# SCH_shield_test_2024-01-20.net
KiCad netlist of a schematic drawn in EasyEDA
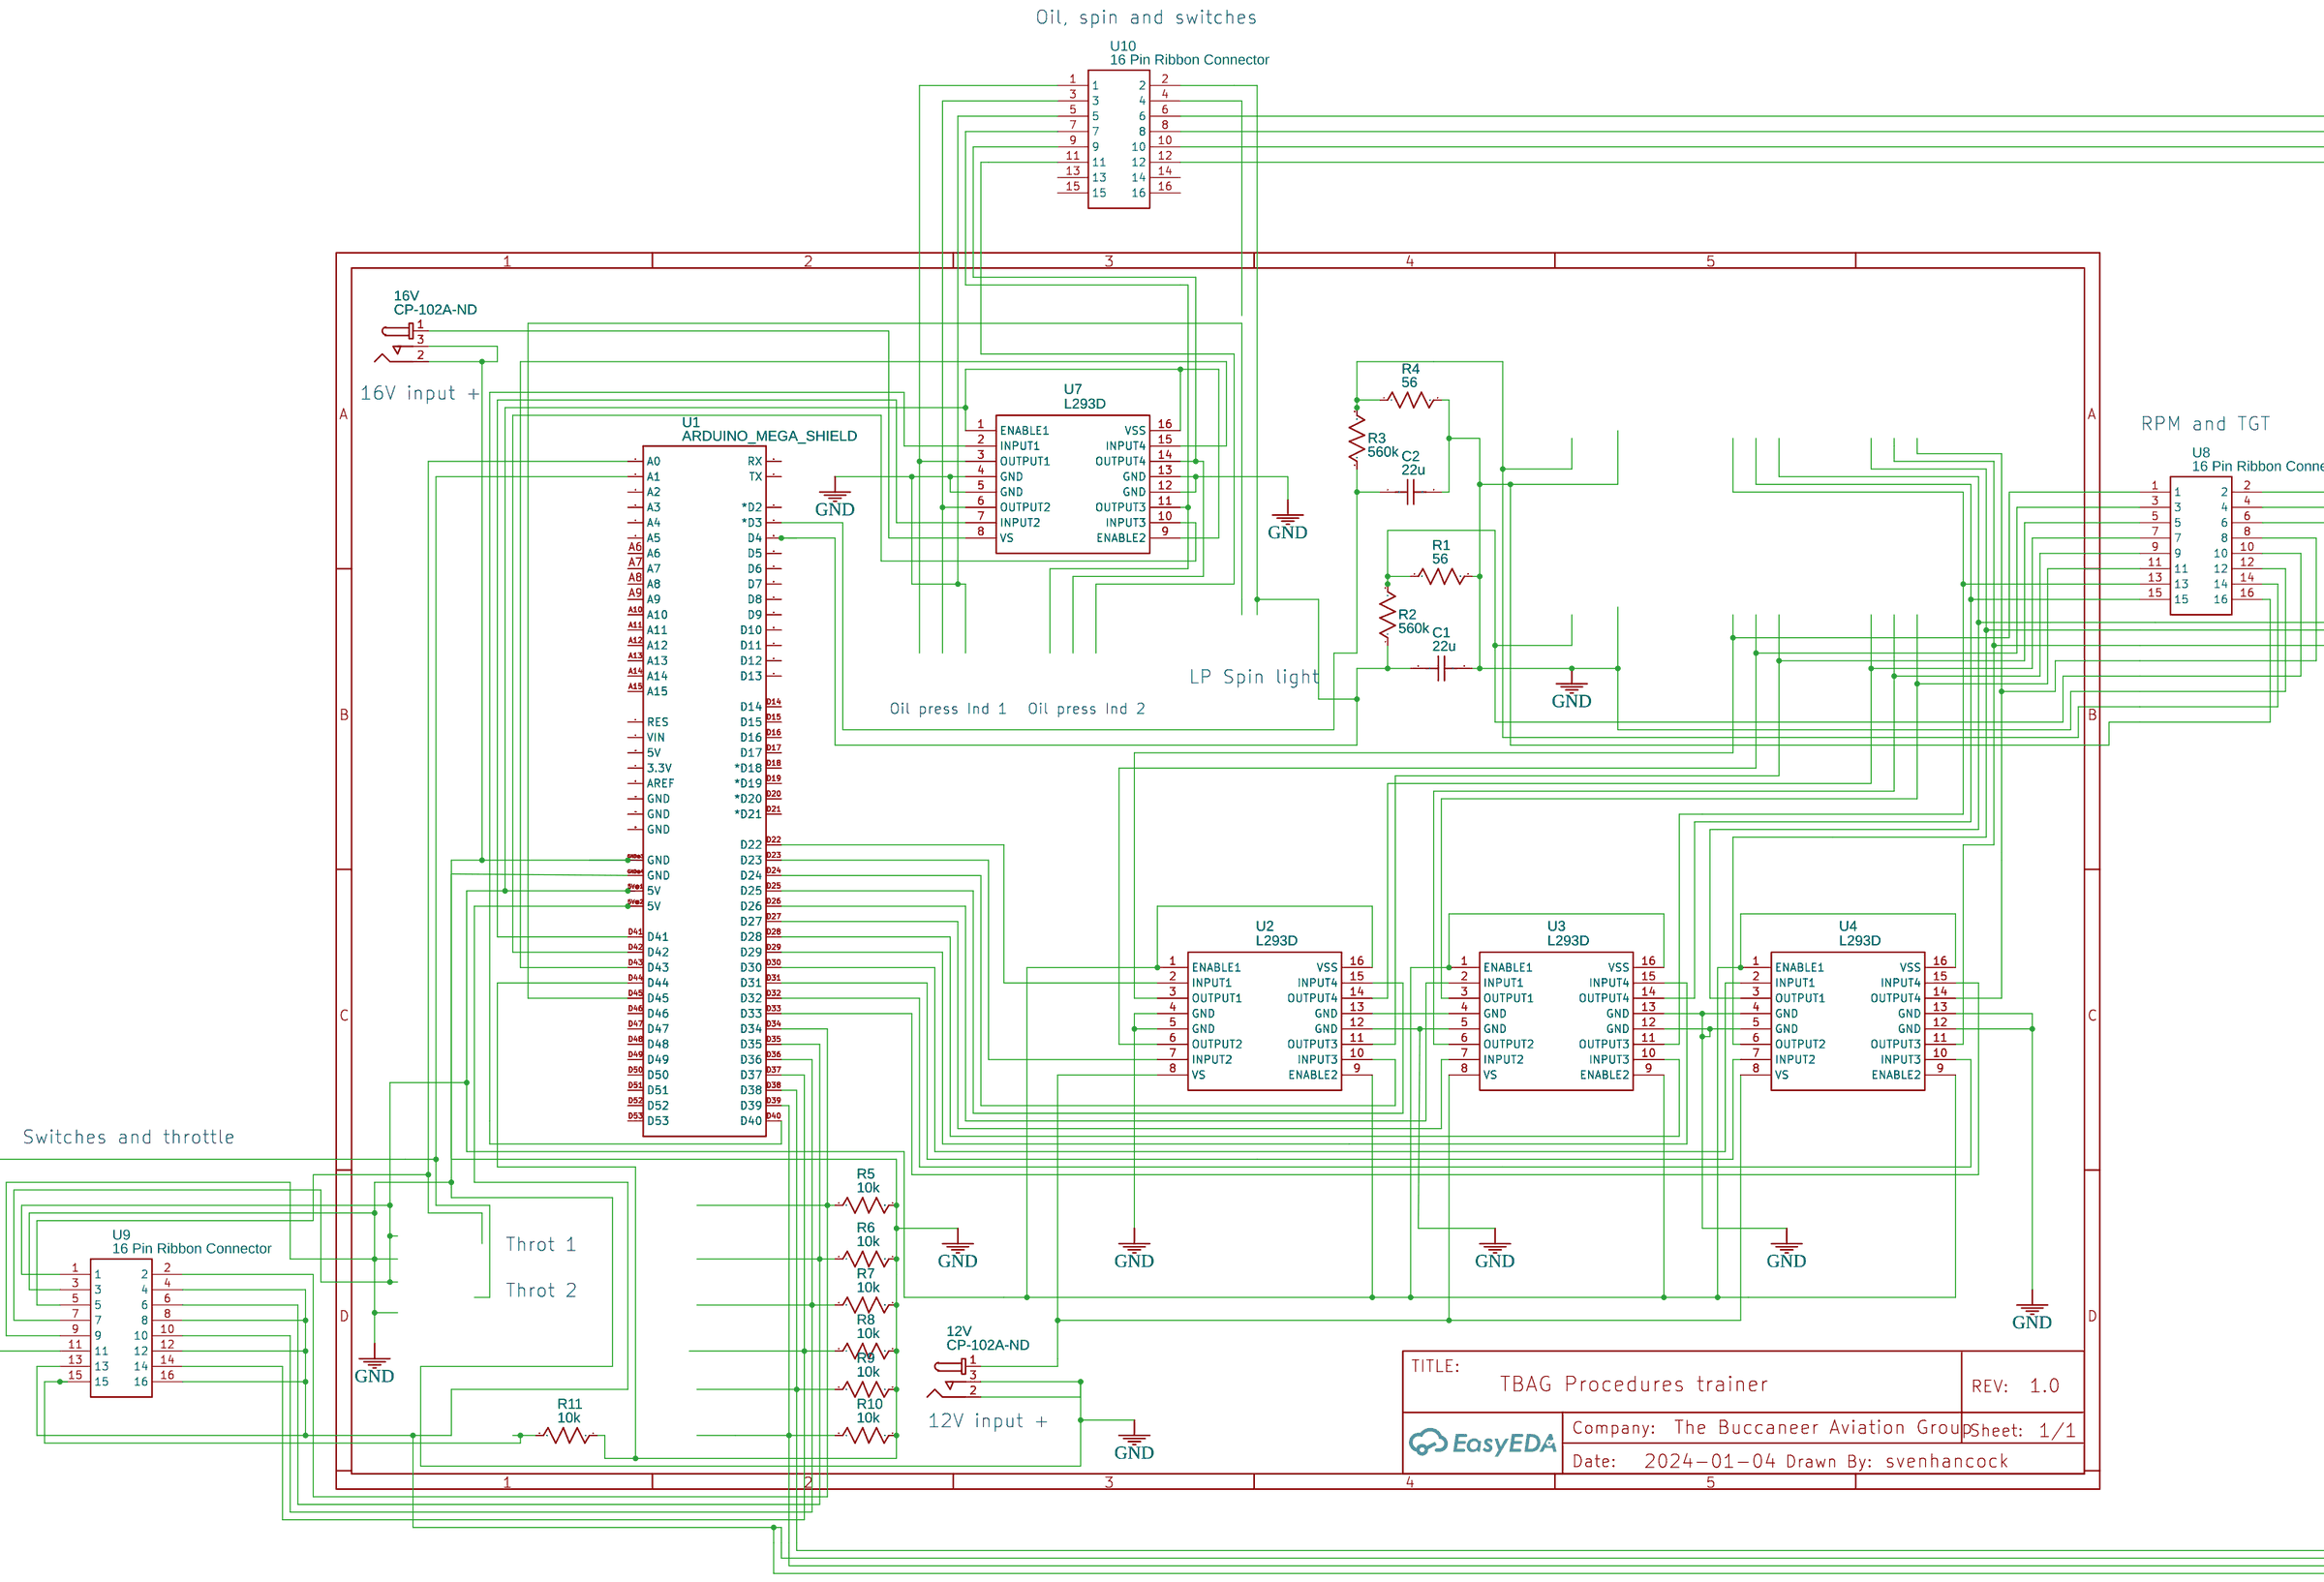
[diagram p0: schematic sheet]

(export (version "E")
  (design (tool "Eeschema 10.0.6"))
  (components
    (comp (ref "12V") (value "CP-102A-ND") (libsource (lib "") (part "CP-102A-ND_1")))
    (comp (ref "16V") (value "CP-102A-ND") (libsource (lib "") (part "CP-102A-ND")))
    (comp (ref "C1") (value "22u") (libsource (lib "") (part "C_0603_US")))
    (comp (ref "C2") (value "22u") (libsource (lib "") (part "C_0603_US")))
    (comp (ref "R1") (value "56") (libsource (lib "") (part "R_0603_US")))
    (comp (ref "R2") (value "560k") (libsource (lib "") (part "R_0603_US_1")))
    (comp (ref "R3") (value "560k") (libsource (lib "") (part "R_0603_US_1")))
    (comp (ref "R4") (value "56") (libsource (lib "") (part "R_0603_US")))
    (comp (ref "R5") (value "10k") (libsource (lib "") (part "R_0603_US")))
    (comp (ref "R6") (value "10k") (libsource (lib "") (part "R_0603_US")))
    (comp (ref "R7") (value "10k") (libsource (lib "") (part "R_0603_US")))
    (comp (ref "R8") (value "10k") (libsource (lib "") (part "R_0603_US")))
    (comp (ref "R9") (value "10k") (libsource (lib "") (part "R_0603_US")))
    (comp (ref "R10") (value "10k") (libsource (lib "") (part "R_0603_US")))
    (comp (ref "R11") (value "10k") (libsource (lib "") (part "R_0603_US")))
    (comp (ref "U1") (value "ARDUINO_MEGA_SHIELD") (libsource (lib "") (part "ARDUINO_MEGA_SHIELD")))
    (comp (ref "U2")
      (value "L293D")
      (fields (field (name "Manufacturer") "ST(意法半导体)"))
      (libsource (lib "") (part "L293D"))
    )
    (comp (ref "U3")
      (value "L293D")
      (fields (field (name "Manufacturer") "ST(意法半导体)"))
      (libsource (lib "") (part "L293D"))
    )
    (comp (ref "U4")
      (value "L293D")
      (fields (field (name "Manufacturer") "ST(意法半导体)"))
      (libsource (lib "") (part "L293D"))
    )
    (comp (ref "U7")
      (value "L293D")
      (fields (field (name "Manufacturer") "ST(意法半导体)"))
      (libsource (lib "") (part "L293D"))
    )
    (comp (ref "U8") (value "16 Pin Ribbon Connector") (libsource (lib "") (part "16 Pin Ribbon Connector")))
    (comp (ref "U9") (value "16 Pin Ribbon Connector") (libsource (lib "") (part "16 Pin Ribbon Connector")))
    (comp (ref "U10") (value "16 Pin Ribbon Connector") (libsource (lib "") (part "16 Pin Ribbon Connector")))
  )
  (nets
    (net (code "1") (name "GND") (class "Default")
      (node (ref "12V") (pin "2") (pintype "unspecified"))
      (node (ref "12V") (pin "3") (pintype "unspecified"))
      (node (ref "16V") (pin "2") (pintype "unspecified"))
      (node (ref "16V") (pin "3") (pintype "unspecified"))
      (node (ref "C1") (pin "2") (pinfunction "2_2") (pintype "unspecified"))
      (node (ref "C2") (pin "2") (pinfunction "2_2") (pintype "unspecified"))
      (node (ref "R1") (pin "2") (pinfunction "2_2") (pintype "unspecified"))
      (node (ref "R10") (pin "2") (pinfunction "2_2") (pintype "unspecified"))
      (node (ref "R11") (pin "2") (pinfunction "2_2") (pintype "unspecified"))
      (node (ref "R4") (pin "2") (pinfunction "2_2") (pintype "unspecified"))
      (node (ref "R5") (pin "2") (pinfunction "2_2") (pintype "unspecified"))
      (node (ref "R6") (pin "2") (pinfunction "2_2") (pintype "unspecified"))
      (node (ref "R7") (pin "2") (pinfunction "2_2") (pintype "unspecified"))
      (node (ref "R8") (pin "2") (pinfunction "2_2") (pintype "unspecified"))
      (node (ref "R9") (pin "2") (pinfunction "2_2") (pintype "unspecified"))
      (node (ref "U1") (pin "D44") (pinfunction "D44_D44") (pintype "unspecified"))
      (node (ref "U1") (pin "GND@3") (pinfunction "GND_GND@3") (pintype "unspecified"))
      (node (ref "U10") (pin "5") (pinfunction "5_5") (pintype "unspecified"))
      (node (ref "U2") (pin "12") (pinfunction "GND_12") (pintype "unspecified"))
      (node (ref "U2") (pin "4") (pinfunction "GND_4") (pintype "unspecified"))
      (node (ref "U2") (pin "5") (pinfunction "GND_5") (pintype "unspecified"))
      (node (ref "U3") (pin "12") (pinfunction "GND_12") (pintype "unspecified"))
      (node (ref "U3") (pin "13") (pinfunction "GND_13") (pintype "unspecified"))
      (node (ref "U3") (pin "5") (pinfunction "GND_5") (pintype "unspecified"))
      (node (ref "U4") (pin "12") (pinfunction "GND_12") (pintype "unspecified"))
      (node (ref "U4") (pin "13") (pinfunction "GND_13") (pintype "unspecified"))
      (node (ref "U4") (pin "4") (pinfunction "GND_4") (pintype "unspecified"))
      (node (ref "U4") (pin "5") (pinfunction "GND_5") (pintype "unspecified"))
      (node (ref "U7") (pin "12") (pinfunction "GND_12") (pintype "unspecified"))
      (node (ref "U7") (pin "13") (pinfunction "GND_13") (pintype "unspecified"))
      (node (ref "U7") (pin "4") (pinfunction "GND_4") (pintype "unspecified"))
      (node (ref "U7") (pin "5") (pinfunction "GND_5") (pintype "unspecified"))
      (node (ref "U8") (pin "12") (pinfunction "12_12") (pintype "unspecified"))
      (node (ref "U8") (pin "16") (pinfunction "16_16") (pintype "unspecified"))
      (node (ref "U9") (pin "3") (pinfunction "3_3") (pintype "unspecified"))
      (node (ref "U9") (pin "9") (pinfunction "9_9") (pintype "unspecified"))
    )
    (net (code "2") (name "Net-(C1-Pad1)") (class "Default")
      (node (ref "C1") (pin "1") (pinfunction "1_1") (pintype "unspecified"))
      (node (ref "R2") (pin "1") (pinfunction "1_1") (pintype "unspecified"))
      (node (ref "U1") (pin "D4") (pinfunction "D4_D4") (pintype "unspecified"))
      (node (ref "U10") (pin "2") (pinfunction "2_2") (pintype "unspecified"))
    )
    (net (code "3") (name "Net-(R1-Pad1)") (class "Default")
      (node (ref "R1") (pin "1") (pinfunction "1_1") (pintype "unspecified"))
      (node (ref "R2") (pin "2") (pinfunction "2_2") (pintype "unspecified"))
      (node (ref "U8") (pin "10") (pinfunction "10_10") (pintype "unspecified"))
    )
    (net (code "4") (name "Net-(R3-Pad2)") (class "Default")
      (node (ref "R3") (pin "2") (pinfunction "2_2") (pintype "unspecified"))
      (node (ref "R4") (pin "1") (pinfunction "1_1") (pintype "unspecified"))
      (node (ref "U8") (pin "14") (pinfunction "14_14") (pintype "unspecified"))
    )
    (net (code "5") (name "Net-(R5-Pad1)") (class "Default")
      (node (ref "R5") (pin "1") (pinfunction "1_1") (pintype "unspecified"))
      (node (ref "U1") (pin "D34") (pinfunction "D34_D34") (pintype "unspecified"))
      (node (ref "U9") (pin "2") (pinfunction "2_2") (pintype "unspecified"))
    )
    (net (code "6") (name "Net-(R6-Pad1)") (class "Default")
      (node (ref "R6") (pin "1") (pinfunction "1_1") (pintype "unspecified"))
      (node (ref "U1") (pin "D35") (pinfunction "D35_D35") (pintype "unspecified"))
      (node (ref "U9") (pin "6") (pinfunction "6_6") (pintype "unspecified"))
    )
    (net (code "7") (name "Net-(R7-Pad1)") (class "Default")
      (node (ref "R7") (pin "1") (pinfunction "1_1") (pintype "unspecified"))
      (node (ref "U1") (pin "D36") (pinfunction "D36_D36") (pintype "unspecified"))
      (node (ref "U9") (pin "10") (pinfunction "10_10") (pintype "unspecified"))
    )
    (net (code "8") (name "Net-(R8-Pad1)") (class "Default")
      (node (ref "R8") (pin "1") (pinfunction "1_1") (pintype "unspecified"))
      (node (ref "U1") (pin "D37") (pinfunction "D37_D37") (pintype "unspecified"))
      (node (ref "U9") (pin "14") (pinfunction "14_14") (pintype "unspecified"))
    )
    (net (code "9") (name "Net-(R9-Pad1)") (class "Default")
      (node (ref "R9") (pin "1") (pinfunction "1_1") (pintype "unspecified"))
      (node (ref "U1") (pin "D38") (pinfunction "D38_D38") (pintype "unspecified"))
      (node (ref "U10") (pin "6") (pinfunction "6_6") (pintype "unspecified"))
    )
    (net (code "10") (name "Net-(R10-Pad1)") (class "Default")
      (node (ref "R10") (pin "1") (pinfunction "1_1") (pintype "unspecified"))
      (node (ref "U1") (pin "D39") (pinfunction "D39_D39") (pintype "unspecified"))
      (node (ref "U10") (pin "10") (pinfunction "10_10") (pintype "unspecified"))
    )
    (net (code "11") (name "Net-(R11-Pad1)") (class "Default")
      (node (ref "R11") (pin "1") (pinfunction "1_1") (pintype "unspecified"))
      (node (ref "U9") (pin "15") (pinfunction "15_15") (pintype "unspecified"))
    )
    (net (code "12") (name "Net-(U1-*D3)") (class "Default")
      (node (ref "C2") (pin "1") (pinfunction "1_1") (pintype "unspecified"))
      (node (ref "R3") (pin "1") (pinfunction "1_1") (pintype "unspecified"))
      (node (ref "U1") (pin "D3") (pinfunction "*D3_D3") (pintype "unspecified"))
    )
    (net (code "13") (name "Net-(U1-5V-Pad5V@2)") (class "Default")
      (node (ref "U1") (pin "5V@2") (pinfunction "5V_5V@2") (pintype "unspecified"))
      (node (ref "U10") (pin "12") (pinfunction "12_12") (pintype "unspecified"))
      (node (ref "U10") (pin "8") (pinfunction "8_8") (pintype "unspecified"))
      (node (ref "U9") (pin "12") (pinfunction "12_12") (pintype "unspecified"))
      (node (ref "U9") (pin "13") (pinfunction "13_13") (pintype "unspecified"))
      (node (ref "U9") (pin "16") (pinfunction "16_16") (pintype "unspecified"))
      (node (ref "U9") (pin "4") (pinfunction "4_4") (pintype "unspecified"))
      (node (ref "U9") (pin "8") (pinfunction "8_8") (pintype "unspecified"))
    )
    (net (code "14") (name "Net-(U1-PadA0)") (class "Default")
      (node (ref "U1") (pin "A0") (pinfunction "A0_A0") (pintype "unspecified"))
      (node (ref "U9") (pin "5") (pinfunction "5_5") (pintype "unspecified"))
    )
    (net (code "15") (name "Net-(U1-PadA1)") (class "Default")
      (node (ref "U1") (pin "A1") (pinfunction "A1_A1") (pintype "unspecified"))
      (node (ref "U9") (pin "11") (pinfunction "11_11") (pintype "unspecified"))
    )
    (net (code "16") (name "Net-(U2-ENABLE1)") (class "Default")
      (node (ref "U1") (pin "5V@1") (pinfunction "5V_5V@1") (pintype "unspecified"))
      (node (ref "U2") (pin "1") (pinfunction "ENABLE1_1") (pintype "unspecified"))
      (node (ref "U2") (pin "16") (pinfunction "VSS_16") (pintype "unspecified"))
      (node (ref "U2") (pin "9") (pinfunction "ENABLE2_9") (pintype "unspecified"))
      (node (ref "U3") (pin "1") (pinfunction "ENABLE1_1") (pintype "unspecified"))
      (node (ref "U3") (pin "16") (pinfunction "VSS_16") (pintype "unspecified"))
      (node (ref "U3") (pin "9") (pinfunction "ENABLE2_9") (pintype "unspecified"))
      (node (ref "U4") (pin "1") (pinfunction "ENABLE1_1") (pintype "unspecified"))
      (node (ref "U4") (pin "16") (pinfunction "VSS_16") (pintype "unspecified"))
      (node (ref "U4") (pin "9") (pinfunction "ENABLE2_9") (pintype "unspecified"))
      (node (ref "U7") (pin "1") (pinfunction "ENABLE1_1") (pintype "unspecified"))
      (node (ref "U7") (pin "16") (pinfunction "VSS_16") (pintype "unspecified"))
      (node (ref "U7") (pin "9") (pinfunction "ENABLE2_9") (pintype "unspecified"))
      (node (ref "U9") (pin "1") (pinfunction "1_1") (pintype "unspecified"))
      (node (ref "U9") (pin "7") (pinfunction "7_7") (pintype "unspecified"))
    )
    (net (code "17") (name "Net-(U2-GND-Pad13)") (class "Default")
      (node (ref "U2") (pin "13") (pinfunction "GND_13") (pintype "unspecified"))
      (node (ref "U3") (pin "4") (pinfunction "GND_4") (pintype "unspecified"))
    )
    (net (code "18") (name "Net-(U2-INPUT1)") (class "Default")
      (node (ref "U1") (pin "D22") (pinfunction "D22_D22") (pintype "unspecified"))
      (node (ref "U2") (pin "2") (pinfunction "INPUT1_2") (pintype "unspecified"))
    )
    (net (code "19") (name "Net-(U2-INPUT2)") (class "Default")
      (node (ref "U1") (pin "D23") (pinfunction "D23_D23") (pintype "unspecified"))
      (node (ref "U2") (pin "7") (pinfunction "INPUT2_7") (pintype "unspecified"))
    )
    (net (code "20") (name "Net-(U2-INPUT3)") (class "Default")
      (node (ref "U1") (pin "D24") (pinfunction "D24_D24") (pintype "unspecified"))
      (node (ref "U2") (pin "10") (pinfunction "INPUT3_10") (pintype "unspecified"))
    )
    (net (code "21") (name "Net-(U2-INPUT4)") (class "Default")
      (node (ref "U1") (pin "D25") (pinfunction "D25_D25") (pintype "unspecified"))
      (node (ref "U2") (pin "15") (pinfunction "INPUT4_15") (pintype "unspecified"))
    )
    (net (code "22") (name "Net-(U2-OUTPUT1)") (class "Default")
      (node (ref "U2") (pin "3") (pinfunction "OUTPUT1_3") (pintype "unspecified"))
      (node (ref "U8") (pin "1") (pinfunction "1_1") (pintype "unspecified"))
    )
    (net (code "23") (name "Net-(U2-OUTPUT2)") (class "Default")
      (node (ref "U2") (pin "6") (pinfunction "OUTPUT2_6") (pintype "unspecified"))
      (node (ref "U8") (pin "3") (pinfunction "3_3") (pintype "unspecified"))
    )
    (net (code "24") (name "Net-(U2-OUTPUT3)") (class "Default")
      (node (ref "U2") (pin "11") (pinfunction "OUTPUT3_11") (pintype "unspecified"))
      (node (ref "U8") (pin "5") (pinfunction "5_5") (pintype "unspecified"))
    )
    (net (code "25") (name "Net-(U2-OUTPUT4)") (class "Default")
      (node (ref "U2") (pin "14") (pinfunction "OUTPUT4_14") (pintype "unspecified"))
      (node (ref "U8") (pin "7") (pinfunction "7_7") (pintype "unspecified"))
    )
    (net (code "26") (name "Net-(U2-VS)") (class "Default")
      (node (ref "12V") (pin "1") (pintype "unspecified"))
      (node (ref "U2") (pin "8") (pinfunction "VS_8") (pintype "unspecified"))
      (node (ref "U3") (pin "8") (pinfunction "VS_8") (pintype "unspecified"))
      (node (ref "U4") (pin "8") (pinfunction "VS_8") (pintype "unspecified"))
    )
    (net (code "27") (name "Net-(U3-INPUT1)") (class "Default")
      (node (ref "U1") (pin "D26") (pinfunction "D26_D26") (pintype "unspecified"))
      (node (ref "U3") (pin "2") (pinfunction "INPUT1_2") (pintype "unspecified"))
    )
    (net (code "28") (name "Net-(U3-INPUT2)") (class "Default")
      (node (ref "U1") (pin "D27") (pinfunction "D27_D27") (pintype "unspecified"))
      (node (ref "U3") (pin "7") (pinfunction "INPUT2_7") (pintype "unspecified"))
    )
    (net (code "29") (name "Net-(U3-INPUT3)") (class "Default")
      (node (ref "U1") (pin "D28") (pinfunction "D28_D28") (pintype "unspecified"))
      (node (ref "U3") (pin "10") (pinfunction "INPUT3_10") (pintype "unspecified"))
    )
    (net (code "30") (name "Net-(U3-INPUT4)") (class "Default")
      (node (ref "U1") (pin "D29") (pinfunction "D29_D29") (pintype "unspecified"))
      (node (ref "U3") (pin "15") (pinfunction "INPUT4_15") (pintype "unspecified"))
    )
    (net (code "31") (name "Net-(U3-OUTPUT1)") (class "Default")
      (node (ref "U3") (pin "3") (pinfunction "OUTPUT1_3") (pintype "unspecified"))
      (node (ref "U8") (pin "11") (pinfunction "11_11") (pintype "unspecified"))
    )
    (net (code "32") (name "Net-(U3-OUTPUT2)") (class "Default")
      (node (ref "U3") (pin "6") (pinfunction "OUTPUT2_6") (pintype "unspecified"))
      (node (ref "U8") (pin "9") (pinfunction "9_9") (pintype "unspecified"))
    )
    (net (code "33") (name "Net-(U3-OUTPUT3)") (class "Default")
      (node (ref "U3") (pin "11") (pinfunction "OUTPUT3_11") (pintype "unspecified"))
      (node (ref "U8") (pin "13") (pinfunction "13_13") (pintype "unspecified"))
    )
    (net (code "34") (name "Net-(U3-OUTPUT4)") (class "Default")
      (node (ref "U3") (pin "14") (pinfunction "OUTPUT4_14") (pintype "unspecified"))
      (node (ref "U8") (pin "15") (pinfunction "15_15") (pintype "unspecified"))
    )
    (net (code "35") (name "Net-(U4-INPUT1)") (class "Default")
      (node (ref "U1") (pin "D30") (pinfunction "D30_D30") (pintype "unspecified"))
      (node (ref "U4") (pin "2") (pinfunction "INPUT1_2") (pintype "unspecified"))
    )
    (net (code "36") (name "Net-(U4-INPUT2)") (class "Default")
      (node (ref "U1") (pin "D31") (pinfunction "D31_D31") (pintype "unspecified"))
      (node (ref "U4") (pin "7") (pinfunction "INPUT2_7") (pintype "unspecified"))
    )
    (net (code "37") (name "Net-(U4-INPUT3)") (class "Default")
      (node (ref "U1") (pin "D32") (pinfunction "D32_D32") (pintype "unspecified"))
      (node (ref "U4") (pin "10") (pinfunction "INPUT3_10") (pintype "unspecified"))
    )
    (net (code "38") (name "Net-(U4-INPUT4)") (class "Default")
      (node (ref "U1") (pin "D33") (pinfunction "D33_D33") (pintype "unspecified"))
      (node (ref "U4") (pin "15") (pinfunction "INPUT4_15") (pintype "unspecified"))
    )
    (net (code "39") (name "Net-(U4-OUTPUT1)") (class "Default")
      (node (ref "U4") (pin "3") (pinfunction "OUTPUT1_3") (pintype "unspecified"))
      (node (ref "U8") (pin "2") (pinfunction "2_2") (pintype "unspecified"))
    )
    (net (code "40") (name "Net-(U4-OUTPUT2)") (class "Default")
      (node (ref "U4") (pin "6") (pinfunction "OUTPUT2_6") (pintype "unspecified"))
      (node (ref "U8") (pin "4") (pinfunction "4_4") (pintype "unspecified"))
    )
    (net (code "41") (name "Net-(U4-OUTPUT3)") (class "Default")
      (node (ref "U4") (pin "11") (pinfunction "OUTPUT3_11") (pintype "unspecified"))
      (node (ref "U8") (pin "6") (pinfunction "6_6") (pintype "unspecified"))
    )
    (net (code "42") (name "Net-(U4-OUTPUT4)") (class "Default")
      (node (ref "U4") (pin "14") (pinfunction "OUTPUT4_14") (pintype "unspecified"))
      (node (ref "U8") (pin "8") (pinfunction "8_8") (pintype "unspecified"))
    )
    (net (code "43") (name "Net-(U7-INPUT1)") (class "Default")
      (node (ref "U1") (pin "D40") (pinfunction "D40_D40") (pintype "unspecified"))
      (node (ref "U7") (pin "2") (pinfunction "INPUT1_2") (pintype "unspecified"))
    )
    (net (code "44") (name "Net-(U7-INPUT2)") (class "Default")
      (node (ref "U1") (pin "D41") (pinfunction "D41_D41") (pintype "unspecified"))
      (node (ref "U7") (pin "7") (pinfunction "INPUT2_7") (pintype "unspecified"))
    )
    (net (code "45") (name "Net-(U7-INPUT3)") (class "Default")
      (node (ref "U1") (pin "D42") (pinfunction "D42_D42") (pintype "unspecified"))
      (node (ref "U7") (pin "10") (pinfunction "INPUT3_10") (pintype "unspecified"))
    )
    (net (code "46") (name "Net-(U7-INPUT4)") (class "Default")
      (node (ref "U1") (pin "D43") (pinfunction "D43_D43") (pintype "unspecified"))
      (node (ref "U7") (pin "15") (pinfunction "INPUT4_15") (pintype "unspecified"))
    )
    (net (code "47") (name "Net-(U7-OUTPUT1)") (class "Default")
      (node (ref "U10") (pin "1") (pinfunction "1_1") (pintype "unspecified"))
      (node (ref "U7") (pin "3") (pinfunction "OUTPUT1_3") (pintype "unspecified"))
    )
    (net (code "48") (name "Net-(U7-OUTPUT2)") (class "Default")
      (node (ref "U10") (pin "3") (pinfunction "3_3") (pintype "unspecified"))
      (node (ref "U7") (pin "6") (pinfunction "OUTPUT2_6") (pintype "unspecified"))
    )
    (net (code "49") (name "Net-(U7-OUTPUT3)") (class "Default")
      (node (ref "U10") (pin "7") (pinfunction "7_7") (pintype "unspecified"))
      (node (ref "U7") (pin "11") (pinfunction "OUTPUT3_11") (pintype "unspecified"))
    )
    (net (code "50") (name "Net-(U7-OUTPUT4)") (class "Default")
      (node (ref "U10") (pin "9") (pinfunction "9_9") (pintype "unspecified"))
      (node (ref "U7") (pin "14") (pinfunction "OUTPUT4_14") (pintype "unspecified"))
    )
    (net (code "51") (name "Net-(U7-VS)") (class "Default")
      (node (ref "16V") (pin "1") (pintype "unspecified"))
      (node (ref "U7") (pin "8") (pinfunction "VS_8") (pintype "unspecified"))
    )
    (net (code "52") (name "unconnected-(U1-*D2-PadD2)") (class "Default")
      (node (ref "U1") (pin "D2") (pinfunction "*D2_D2") (pintype "unspecified"))
    )
    (net (code "53") (name "unconnected-(U1-*D18-PadD18)") (class "Default")
      (node (ref "U1") (pin "D18") (pinfunction "*D18_D18") (pintype "unspecified"))
    )
    (net (code "54") (name "unconnected-(U1-*D19-PadD19)") (class "Default")
      (node (ref "U1") (pin "D19") (pinfunction "*D19_D19") (pintype "unspecified"))
    )
    (net (code "55") (name "unconnected-(U1-*D20-PadD20)") (class "Default")
      (node (ref "U1") (pin "D20") (pinfunction "*D20_D20") (pintype "unspecified"))
    )
    (net (code "56") (name "unconnected-(U1-*D21-PadD21)") (class "Default")
      (node (ref "U1") (pin "D21") (pinfunction "*D21_D21") (pintype "unspecified"))
    )
    (net (code "57") (name "unconnected-(U1-5V-Pad5V@0)") (class "Default")
      (node (ref "U1") (pin "5V@0") (pinfunction "5V_5V@0") (pintype "passive"))
    )
    (net (code "58") (name "unconnected-(U1-GND-PadGND@0)") (class "Default")
      (node (ref "U1") (pin "GND@0") (pinfunction "GND_GND@0") (pintype "unspecified"))
    )
    (net (code "59") (name "unconnected-(U1-GND-PadGND@1)") (class "Default")
      (node (ref "U1") (pin "GND@1") (pinfunction "GND_GND@1") (pintype "unspecified"))
    )
    (net (code "60") (name "unconnected-(U1-GND-PadGND@2)") (class "Default")
      (node (ref "U1") (pin "GND@2") (pinfunction "GND_GND@2") (pintype "unspecified"))
    )
    (net (code "61") (name "unconnected-(U1-GND-PadGND@4)") (class "Default")
      (node (ref "U1") (pin "GND@4") (pinfunction "GND_GND@4") (pintype "unspecified"))
    )
    (net (code "62") (name "unconnected-(U1-Pad3.3V)") (class "Default")
      (node (ref "U1") (pin "3.3V") (pinfunction "3.3V_3.3V") (pintype "unspecified"))
    )
    (net (code "63") (name "unconnected-(U1-PadA2)") (class "Default")
      (node (ref "U1") (pin "A2") (pinfunction "A2_A2") (pintype "unspecified"))
    )
    (net (code "64") (name "unconnected-(U1-PadA3)") (class "Default")
      (node (ref "U1") (pin "A3") (pinfunction "A3_A3") (pintype "unspecified"))
    )
    (net (code "65") (name "unconnected-(U1-PadA4)") (class "Default")
      (node (ref "U1") (pin "A4") (pinfunction "A4_A4") (pintype "unspecified"))
    )
    (net (code "66") (name "unconnected-(U1-PadA5)") (class "Default")
      (node (ref "U1") (pin "A5") (pinfunction "A5_A5") (pintype "unspecified"))
    )
    (net (code "67") (name "unconnected-(U1-PadA6)") (class "Default")
      (node (ref "U1") (pin "A6") (pinfunction "A6_A6") (pintype "unspecified"))
    )
    (net (code "68") (name "unconnected-(U1-PadA7)") (class "Default")
      (node (ref "U1") (pin "A7") (pinfunction "A7_A7") (pintype "unspecified"))
    )
    (net (code "69") (name "unconnected-(U1-PadA8)") (class "Default")
      (node (ref "U1") (pin "A8") (pinfunction "A8_A8") (pintype "unspecified"))
    )
    (net (code "70") (name "unconnected-(U1-PadA9)") (class "Default")
      (node (ref "U1") (pin "A9") (pinfunction "A9_A9") (pintype "unspecified"))
    )
    (net (code "71") (name "unconnected-(U1-PadA10)") (class "Default")
      (node (ref "U1") (pin "A10") (pinfunction "A10_A10") (pintype "unspecified"))
    )
    (net (code "72") (name "unconnected-(U1-PadA11)") (class "Default")
      (node (ref "U1") (pin "A11") (pinfunction "A11_A11") (pintype "unspecified"))
    )
    (net (code "73") (name "unconnected-(U1-PadA12)") (class "Default")
      (node (ref "U1") (pin "A12") (pinfunction "A12_A12") (pintype "unspecified"))
    )
    (net (code "74") (name "unconnected-(U1-PadA13)") (class "Default")
      (node (ref "U1") (pin "A13") (pinfunction "A13_A13") (pintype "unspecified"))
    )
    (net (code "75") (name "unconnected-(U1-PadA14)") (class "Default")
      (node (ref "U1") (pin "A14") (pinfunction "A14_A14") (pintype "unspecified"))
    )
    (net (code "76") (name "unconnected-(U1-PadA15)") (class "Default")
      (node (ref "U1") (pin "A15") (pinfunction "A15_A15") (pintype "unspecified"))
    )
    (net (code "77") (name "unconnected-(U1-PadAREF)") (class "Default")
      (node (ref "U1") (pin "AREF") (pinfunction "AREF_AREF") (pintype "unspecified"))
    )
    (net (code "78") (name "unconnected-(U1-PadD5)") (class "Default")
      (node (ref "U1") (pin "D5") (pinfunction "D5_D5") (pintype "unspecified"))
    )
    (net (code "79") (name "unconnected-(U1-PadD6)") (class "Default")
      (node (ref "U1") (pin "D6") (pinfunction "D6_D6") (pintype "unspecified"))
    )
    (net (code "80") (name "unconnected-(U1-PadD7)") (class "Default")
      (node (ref "U1") (pin "D7") (pinfunction "D7_D7") (pintype "unspecified"))
    )
    (net (code "81") (name "unconnected-(U1-PadD8)") (class "Default")
      (node (ref "U1") (pin "D8") (pinfunction "D8_D8") (pintype "unspecified"))
    )
    (net (code "82") (name "unconnected-(U1-PadD9)") (class "Default")
      (node (ref "U1") (pin "D9") (pinfunction "D9_D9") (pintype "unspecified"))
    )
    (net (code "83") (name "unconnected-(U1-PadD10)") (class "Default")
      (node (ref "U1") (pin "D10") (pinfunction "D10_D10") (pintype "unspecified"))
    )
    (net (code "84") (name "unconnected-(U1-PadD11)") (class "Default")
      (node (ref "U1") (pin "D11") (pinfunction "D11_D11") (pintype "unspecified"))
    )
    (net (code "85") (name "unconnected-(U1-PadD12)") (class "Default")
      (node (ref "U1") (pin "D12") (pinfunction "D12_D12") (pintype "unspecified"))
    )
    (net (code "86") (name "unconnected-(U1-PadD13)") (class "Default")
      (node (ref "U1") (pin "D13") (pinfunction "D13_D13") (pintype "unspecified"))
    )
    (net (code "87") (name "unconnected-(U1-PadD14)") (class "Default")
      (node (ref "U1") (pin "D14") (pinfunction "D14_D14") (pintype "unspecified"))
    )
    (net (code "88") (name "unconnected-(U1-PadD15)") (class "Default")
      (node (ref "U1") (pin "D15") (pinfunction "D15_D15") (pintype "unspecified"))
    )
    (net (code "89") (name "unconnected-(U1-PadD16)") (class "Default")
      (node (ref "U1") (pin "D16") (pinfunction "D16_D16") (pintype "unspecified"))
    )
    (net (code "90") (name "unconnected-(U1-PadD17)") (class "Default")
      (node (ref "U1") (pin "D17") (pinfunction "D17_D17") (pintype "unspecified"))
    )
    (net (code "91") (name "unconnected-(U1-PadD45)") (class "Default")
      (node (ref "U1") (pin "D45") (pinfunction "D45_D45") (pintype "unspecified"))
    )
    (net (code "92") (name "unconnected-(U1-PadD46)") (class "Default")
      (node (ref "U1") (pin "D46") (pinfunction "D46_D46") (pintype "unspecified"))
    )
    (net (code "93") (name "unconnected-(U1-PadD47)") (class "Default")
      (node (ref "U1") (pin "D47") (pinfunction "D47_D47") (pintype "unspecified"))
    )
    (net (code "94") (name "unconnected-(U1-PadD48)") (class "Default")
      (node (ref "U1") (pin "D48") (pinfunction "D48_D48") (pintype "unspecified"))
    )
    (net (code "95") (name "unconnected-(U1-PadD49)") (class "Default")
      (node (ref "U1") (pin "D49") (pinfunction "D49_D49") (pintype "unspecified"))
    )
    (net (code "96") (name "unconnected-(U1-PadD50)") (class "Default")
      (node (ref "U1") (pin "D50") (pinfunction "D50_D50") (pintype "unspecified"))
    )
    (net (code "97") (name "unconnected-(U1-PadD51)") (class "Default")
      (node (ref "U1") (pin "D51") (pinfunction "D51_D51") (pintype "unspecified"))
    )
    (net (code "98") (name "unconnected-(U1-PadD52)") (class "Default")
      (node (ref "U1") (pin "D52") (pinfunction "D52_D52") (pintype "unspecified"))
    )
    (net (code "99") (name "unconnected-(U1-PadD53)") (class "Default")
      (node (ref "U1") (pin "D53") (pinfunction "D53_D53") (pintype "unspecified"))
    )
    (net (code "100") (name "unconnected-(U1-PadRES)") (class "Default")
      (node (ref "U1") (pin "RES") (pinfunction "RES_RES") (pintype "unspecified"))
    )
    (net (code "101") (name "unconnected-(U1-PadRX)") (class "Default")
      (node (ref "U1") (pin "RX") (pinfunction "RX_RX") (pintype "unspecified"))
    )
    (net (code "102") (name "unconnected-(U1-PadTX)") (class "Default")
      (node (ref "U1") (pin "TX") (pinfunction "TX_TX") (pintype "unspecified"))
    )
    (net (code "103") (name "unconnected-(U1-PadVIN)") (class "Default")
      (node (ref "U1") (pin "VIN") (pinfunction "VIN_VIN") (pintype "unspecified"))
    )
    (net (code "104") (name "unconnected-(U10-Pad4)") (class "Default")
      (node (ref "U10") (pin "4") (pinfunction "4_4") (pintype "unspecified"))
    )
    (net (code "105") (name "unconnected-(U10-Pad11)") (class "Default")
      (node (ref "U10") (pin "11") (pinfunction "11_11") (pintype "unspecified"))
    )
    (net (code "106") (name "unconnected-(U10-Pad13)") (class "Default")
      (node (ref "U10") (pin "13") (pinfunction "13_13") (pintype "unspecified"))
    )
    (net (code "107") (name "unconnected-(U10-Pad14)") (class "Default")
      (node (ref "U10") (pin "14") (pinfunction "14_14") (pintype "unspecified"))
    )
    (net (code "108") (name "unconnected-(U10-Pad15)") (class "Default")
      (node (ref "U10") (pin "15") (pinfunction "15_15") (pintype "unspecified"))
    )
    (net (code "109") (name "unconnected-(U10-Pad16)") (class "Default")
      (node (ref "U10") (pin "16") (pinfunction "16_16") (pintype "unspecified"))
    )
  )
)
